# Fri3D_2018_LEDS_01.net
KiCad netlist of a schematic drawn in Altium Designer
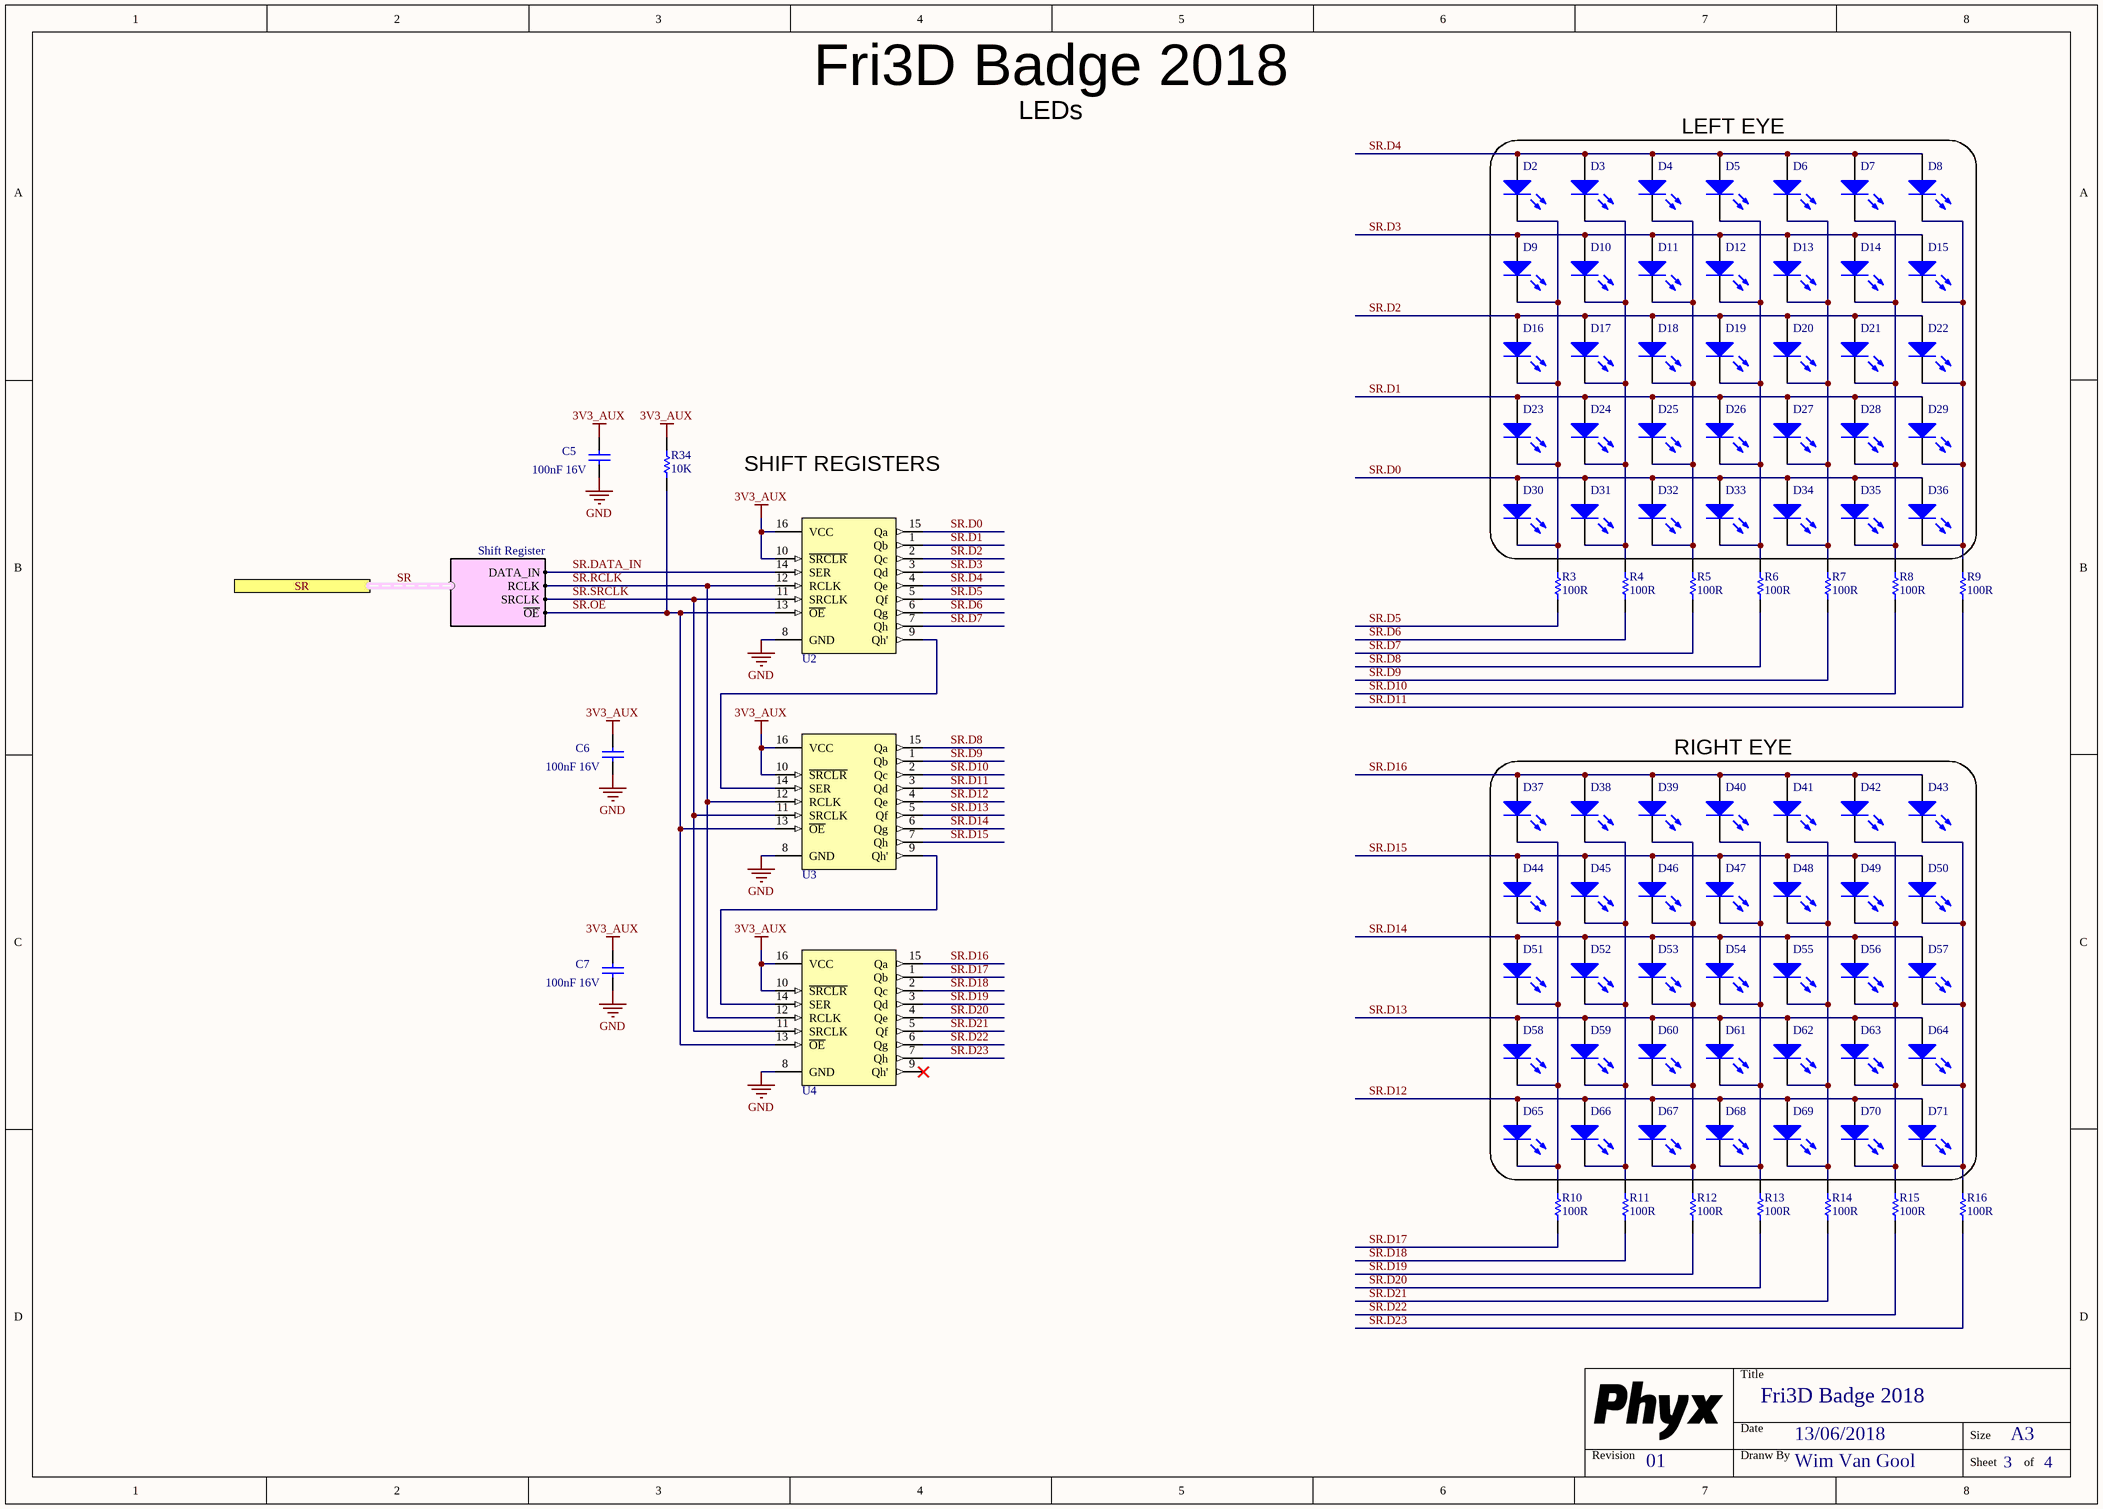
[diagram p0: Fri3D_2018_LEDS_01.SchDoc]

(export (version "E")
  (design (tool "Eeschema 10.0.6"))
  (components
    (comp (ref "C5")
      (value "100nF 16V")
      (footprint "C0603_N")
      (description "Capacitor Ceramic")
      (libsource (lib "Phyx_Components") (part "CAP_CERAMIC"))
    )
    (comp (ref "C6")
      (value "100nF 16V")
      (footprint "C0603_N")
      (description "Capacitor Ceramic")
      (libsource (lib "Phyx_Components") (part "CAP_CERAMIC"))
    )
    (comp (ref "C7")
      (value "100nF 16V")
      (footprint "C0603_N")
      (description "Capacitor Ceramic")
      (libsource (lib "Phyx_Components") (part "CAP_CERAMIC"))
    )
    (comp (ref "D2")
      (value "Default 0805 Blue LED")
      (footprint "LED_0805_BL")
      (description "=Description")
      (libsource (lib "Phyx_Components") (part "LED_BLUE"))
    )
    (comp (ref "D3")
      (value "Default 0805 Blue LED")
      (footprint "LED_0805_BL")
      (description "=Description")
      (libsource (lib "Phyx_Components") (part "LED_BLUE"))
    )
    (comp (ref "D4")
      (value "Default 0805 Blue LED")
      (footprint "LED_0805_BL")
      (description "=Description")
      (libsource (lib "Phyx_Components") (part "LED_BLUE"))
    )
    (comp (ref "D5")
      (value "Default 0805 Blue LED")
      (footprint "LED_0805_BL")
      (description "=Description")
      (libsource (lib "Phyx_Components") (part "LED_BLUE"))
    )
    (comp (ref "D6")
      (value "Default 0805 Blue LED")
      (footprint "LED_0805_BL")
      (description "=Description")
      (libsource (lib "Phyx_Components") (part "LED_BLUE"))
    )
    (comp (ref "D7")
      (value "Default 0805 Blue LED")
      (footprint "LED_0805_BL")
      (description "=Description")
      (libsource (lib "Phyx_Components") (part "LED_BLUE"))
    )
    (comp (ref "D8")
      (value "Default 0805 Blue LED")
      (footprint "LED_0805_BL")
      (description "=Description")
      (libsource (lib "Phyx_Components") (part "LED_BLUE"))
    )
    (comp (ref "D9")
      (value "Default 0805 Blue LED")
      (footprint "LED_0805_BL")
      (description "=Description")
      (libsource (lib "Phyx_Components") (part "LED_BLUE"))
    )
    (comp (ref "D10")
      (value "Default 0805 Blue LED")
      (footprint "LED_0805_BL")
      (description "=Description")
      (libsource (lib "Phyx_Components") (part "LED_BLUE"))
    )
    (comp (ref "D11")
      (value "Default 0805 Blue LED")
      (footprint "LED_0805_BL")
      (description "=Description")
      (libsource (lib "Phyx_Components") (part "LED_BLUE"))
    )
    (comp (ref "D12")
      (value "Default 0805 Blue LED")
      (footprint "LED_0805_BL")
      (description "=Description")
      (libsource (lib "Phyx_Components") (part "LED_BLUE"))
    )
    (comp (ref "D13")
      (value "Default 0805 Blue LED")
      (footprint "LED_0805_BL")
      (description "=Description")
      (libsource (lib "Phyx_Components") (part "LED_BLUE"))
    )
    (comp (ref "D14")
      (value "Default 0805 Blue LED")
      (footprint "LED_0805_BL")
      (description "=Description")
      (libsource (lib "Phyx_Components") (part "LED_BLUE"))
    )
    (comp (ref "D15")
      (value "Default 0805 Blue LED")
      (footprint "LED_0805_BL")
      (description "=Description")
      (libsource (lib "Phyx_Components") (part "LED_BLUE"))
    )
    (comp (ref "D16")
      (value "Default 0805 Blue LED")
      (footprint "LED_0805_BL")
      (description "=Description")
      (libsource (lib "Phyx_Components") (part "LED_BLUE"))
    )
    (comp (ref "D17")
      (value "Default 0805 Blue LED")
      (footprint "LED_0805_BL")
      (description "=Description")
      (libsource (lib "Phyx_Components") (part "LED_BLUE"))
    )
    (comp (ref "D18")
      (value "Default 0805 Blue LED")
      (footprint "LED_0805_BL")
      (description "=Description")
      (libsource (lib "Phyx_Components") (part "LED_BLUE"))
    )
    (comp (ref "D19")
      (value "Default 0805 Blue LED")
      (footprint "LED_0805_BL")
      (description "=Description")
      (libsource (lib "Phyx_Components") (part "LED_BLUE"))
    )
    (comp (ref "D20")
      (value "Default 0805 Blue LED")
      (footprint "LED_0805_BL")
      (description "=Description")
      (libsource (lib "Phyx_Components") (part "LED_BLUE"))
    )
    (comp (ref "D21")
      (value "Default 0805 Blue LED")
      (footprint "LED_0805_BL")
      (description "=Description")
      (libsource (lib "Phyx_Components") (part "LED_BLUE"))
    )
    (comp (ref "D22")
      (value "Default 0805 Blue LED")
      (footprint "LED_0805_BL")
      (description "=Description")
      (libsource (lib "Phyx_Components") (part "LED_BLUE"))
    )
    (comp (ref "D23")
      (value "Default 0805 Blue LED")
      (footprint "LED_0805_BL")
      (description "=Description")
      (libsource (lib "Phyx_Components") (part "LED_BLUE"))
    )
    (comp (ref "D24")
      (value "Default 0805 Blue LED")
      (footprint "LED_0805_BL")
      (description "=Description")
      (libsource (lib "Phyx_Components") (part "LED_BLUE"))
    )
    (comp (ref "D25")
      (value "Default 0805 Blue LED")
      (footprint "LED_0805_BL")
      (description "=Description")
      (libsource (lib "Phyx_Components") (part "LED_BLUE"))
    )
    (comp (ref "D26")
      (value "Default 0805 Blue LED")
      (footprint "LED_0805_BL")
      (description "=Description")
      (libsource (lib "Phyx_Components") (part "LED_BLUE"))
    )
    (comp (ref "D27")
      (value "Default 0805 Blue LED")
      (footprint "LED_0805_BL")
      (description "=Description")
      (libsource (lib "Phyx_Components") (part "LED_BLUE"))
    )
    (comp (ref "D28")
      (value "Default 0805 Blue LED")
      (footprint "LED_0805_BL")
      (description "=Description")
      (libsource (lib "Phyx_Components") (part "LED_BLUE"))
    )
    (comp (ref "D29")
      (value "Default 0805 Blue LED")
      (footprint "LED_0805_BL")
      (description "=Description")
      (libsource (lib "Phyx_Components") (part "LED_BLUE"))
    )
    (comp (ref "D30")
      (value "Default 0805 Blue LED")
      (footprint "LED_0805_BL")
      (description "=Description")
      (libsource (lib "Phyx_Components") (part "LED_BLUE"))
    )
    (comp (ref "D31")
      (value "Default 0805 Blue LED")
      (footprint "LED_0805_BL")
      (description "=Description")
      (libsource (lib "Phyx_Components") (part "LED_BLUE"))
    )
    (comp (ref "D32")
      (value "Default 0805 Blue LED")
      (footprint "LED_0805_BL")
      (description "=Description")
      (libsource (lib "Phyx_Components") (part "LED_BLUE"))
    )
    (comp (ref "D33")
      (value "Default 0805 Blue LED")
      (footprint "LED_0805_BL")
      (description "=Description")
      (libsource (lib "Phyx_Components") (part "LED_BLUE"))
    )
    (comp (ref "D34")
      (value "Default 0805 Blue LED")
      (footprint "LED_0805_BL")
      (description "=Description")
      (libsource (lib "Phyx_Components") (part "LED_BLUE"))
    )
    (comp (ref "D35")
      (value "Default 0805 Blue LED")
      (footprint "LED_0805_BL")
      (description "=Description")
      (libsource (lib "Phyx_Components") (part "LED_BLUE"))
    )
    (comp (ref "D36")
      (value "Default 0805 Blue LED")
      (footprint "LED_0805_BL")
      (description "=Description")
      (libsource (lib "Phyx_Components") (part "LED_BLUE"))
    )
    (comp (ref "D37")
      (value "Default 0805 Blue LED")
      (footprint "LED_0805_BL")
      (description "=Description")
      (libsource (lib "Phyx_Components") (part "LED_BLUE"))
    )
    (comp (ref "D38")
      (value "Default 0805 Blue LED")
      (footprint "LED_0805_BL")
      (description "=Description")
      (libsource (lib "Phyx_Components") (part "LED_BLUE"))
    )
    (comp (ref "D39")
      (value "Default 0805 Blue LED")
      (footprint "LED_0805_BL")
      (description "=Description")
      (libsource (lib "Phyx_Components") (part "LED_BLUE"))
    )
    (comp (ref "D40")
      (value "Default 0805 Blue LED")
      (footprint "LED_0805_BL")
      (description "=Description")
      (libsource (lib "Phyx_Components") (part "LED_BLUE"))
    )
    (comp (ref "D41")
      (value "Default 0805 Blue LED")
      (footprint "LED_0805_BL")
      (description "=Description")
      (libsource (lib "Phyx_Components") (part "LED_BLUE"))
    )
    (comp (ref "D42")
      (value "Default 0805 Blue LED")
      (footprint "LED_0805_BL")
      (description "=Description")
      (libsource (lib "Phyx_Components") (part "LED_BLUE"))
    )
    (comp (ref "D43")
      (value "Default 0805 Blue LED")
      (footprint "LED_0805_BL")
      (description "=Description")
      (libsource (lib "Phyx_Components") (part "LED_BLUE"))
    )
    (comp (ref "D44")
      (value "Default 0805 Blue LED")
      (footprint "LED_0805_BL")
      (description "=Description")
      (libsource (lib "Phyx_Components") (part "LED_BLUE"))
    )
    (comp (ref "D45")
      (value "Default 0805 Blue LED")
      (footprint "LED_0805_BL")
      (description "=Description")
      (libsource (lib "Phyx_Components") (part "LED_BLUE"))
    )
    (comp (ref "D46")
      (value "Default 0805 Blue LED")
      (footprint "LED_0805_BL")
      (description "=Description")
      (libsource (lib "Phyx_Components") (part "LED_BLUE"))
    )
    (comp (ref "D47")
      (value "Default 0805 Blue LED")
      (footprint "LED_0805_BL")
      (description "=Description")
      (libsource (lib "Phyx_Components") (part "LED_BLUE"))
    )
    (comp (ref "D48")
      (value "Default 0805 Blue LED")
      (footprint "LED_0805_BL")
      (description "=Description")
      (libsource (lib "Phyx_Components") (part "LED_BLUE"))
    )
    (comp (ref "D49")
      (value "Default 0805 Blue LED")
      (footprint "LED_0805_BL")
      (description "=Description")
      (libsource (lib "Phyx_Components") (part "LED_BLUE"))
    )
    (comp (ref "D50")
      (value "Default 0805 Blue LED")
      (footprint "LED_0805_BL")
      (description "=Description")
      (libsource (lib "Phyx_Components") (part "LED_BLUE"))
    )
    (comp (ref "D51")
      (value "Default 0805 Blue LED")
      (footprint "LED_0805_BL")
      (description "=Description")
      (libsource (lib "Phyx_Components") (part "LED_BLUE"))
    )
    (comp (ref "D52")
      (value "Default 0805 Blue LED")
      (footprint "LED_0805_BL")
      (description "=Description")
      (libsource (lib "Phyx_Components") (part "LED_BLUE"))
    )
    (comp (ref "D53")
      (value "Default 0805 Blue LED")
      (footprint "LED_0805_BL")
      (description "=Description")
      (libsource (lib "Phyx_Components") (part "LED_BLUE"))
    )
    (comp (ref "D54")
      (value "Default 0805 Blue LED")
      (footprint "LED_0805_BL")
      (description "=Description")
      (libsource (lib "Phyx_Components") (part "LED_BLUE"))
    )
    (comp (ref "D55")
      (value "Default 0805 Blue LED")
      (footprint "LED_0805_BL")
      (description "=Description")
      (libsource (lib "Phyx_Components") (part "LED_BLUE"))
    )
    (comp (ref "D56")
      (value "Default 0805 Blue LED")
      (footprint "LED_0805_BL")
      (description "=Description")
      (libsource (lib "Phyx_Components") (part "LED_BLUE"))
    )
    (comp (ref "D57")
      (value "Default 0805 Blue LED")
      (footprint "LED_0805_BL")
      (description "=Description")
      (libsource (lib "Phyx_Components") (part "LED_BLUE"))
    )
    (comp (ref "D58")
      (value "Default 0805 Blue LED")
      (footprint "LED_0805_BL")
      (description "=Description")
      (libsource (lib "Phyx_Components") (part "LED_BLUE"))
    )
    (comp (ref "D59")
      (value "Default 0805 Blue LED")
      (footprint "LED_0805_BL")
      (description "=Description")
      (libsource (lib "Phyx_Components") (part "LED_BLUE"))
    )
    (comp (ref "D60")
      (value "Default 0805 Blue LED")
      (footprint "LED_0805_BL")
      (description "=Description")
      (libsource (lib "Phyx_Components") (part "LED_BLUE"))
    )
    (comp (ref "D61")
      (value "Default 0805 Blue LED")
      (footprint "LED_0805_BL")
      (description "=Description")
      (libsource (lib "Phyx_Components") (part "LED_BLUE"))
    )
    (comp (ref "D62")
      (value "Default 0805 Blue LED")
      (footprint "LED_0805_BL")
      (description "=Description")
      (libsource (lib "Phyx_Components") (part "LED_BLUE"))
    )
    (comp (ref "D63")
      (value "Default 0805 Blue LED")
      (footprint "LED_0805_BL")
      (description "=Description")
      (libsource (lib "Phyx_Components") (part "LED_BLUE"))
    )
    (comp (ref "D64")
      (value "Default 0805 Blue LED")
      (footprint "LED_0805_BL")
      (description "=Description")
      (libsource (lib "Phyx_Components") (part "LED_BLUE"))
    )
    (comp (ref "D65")
      (value "Default 0805 Blue LED")
      (footprint "LED_0805_BL")
      (description "=Description")
      (libsource (lib "Phyx_Components") (part "LED_BLUE"))
    )
    (comp (ref "D66")
      (value "Default 0805 Blue LED")
      (footprint "LED_0805_BL")
      (description "=Description")
      (libsource (lib "Phyx_Components") (part "LED_BLUE"))
    )
    (comp (ref "D67")
      (value "Default 0805 Blue LED")
      (footprint "LED_0805_BL")
      (description "=Description")
      (libsource (lib "Phyx_Components") (part "LED_BLUE"))
    )
    (comp (ref "D68")
      (value "Default 0805 Blue LED")
      (footprint "LED_0805_BL")
      (description "=Description")
      (libsource (lib "Phyx_Components") (part "LED_BLUE"))
    )
    (comp (ref "D69")
      (value "Default 0805 Blue LED")
      (footprint "LED_0805_BL")
      (description "=Description")
      (libsource (lib "Phyx_Components") (part "LED_BLUE"))
    )
    (comp (ref "D70")
      (value "Default 0805 Blue LED")
      (footprint "LED_0805_BL")
      (description "=Description")
      (libsource (lib "Phyx_Components") (part "LED_BLUE"))
    )
    (comp (ref "D71")
      (value "Default 0805 Blue LED")
      (footprint "LED_0805_BL")
      (description "=Description")
      (libsource (lib "Phyx_Components") (part "LED_BLUE"))
    )
    (comp (ref "R3")
      (value "100R")
      (footprint "R0603_N")
      (fields (field (name "Comment") "RESISTOR"))
      (libsource (lib "Phyx_Components") (part "RESISTOR"))
    )
    (comp (ref "R4")
      (value "100R")
      (footprint "R0603_N")
      (fields (field (name "Comment") "RESISTOR"))
      (libsource (lib "Phyx_Components") (part "RESISTOR"))
    )
    (comp (ref "R5")
      (value "100R")
      (footprint "R0603_N")
      (fields (field (name "Comment") "RESISTOR"))
      (libsource (lib "Phyx_Components") (part "RESISTOR"))
    )
    (comp (ref "R6")
      (value "100R")
      (footprint "R0603_N")
      (fields (field (name "Comment") "RESISTOR"))
      (libsource (lib "Phyx_Components") (part "RESISTOR"))
    )
    (comp (ref "R7")
      (value "100R")
      (footprint "R0603_N")
      (fields (field (name "Comment") "RESISTOR"))
      (libsource (lib "Phyx_Components") (part "RESISTOR"))
    )
    (comp (ref "R8")
      (value "100R")
      (footprint "R0603_N")
      (fields (field (name "Comment") "RESISTOR"))
      (libsource (lib "Phyx_Components") (part "RESISTOR"))
    )
    (comp (ref "R9")
      (value "100R")
      (footprint "R0603_N")
      (fields (field (name "Comment") "RESISTOR"))
      (libsource (lib "Phyx_Components") (part "RESISTOR"))
    )
    (comp (ref "R10")
      (value "100R")
      (footprint "R0603_N")
      (fields (field (name "Comment") "RESISTOR"))
      (libsource (lib "Phyx_Components") (part "RESISTOR"))
    )
    (comp (ref "R11")
      (value "100R")
      (footprint "R0603_N")
      (fields (field (name "Comment") "RESISTOR"))
      (libsource (lib "Phyx_Components") (part "RESISTOR"))
    )
    (comp (ref "R12")
      (value "100R")
      (footprint "R0603_N")
      (fields (field (name "Comment") "RESISTOR"))
      (libsource (lib "Phyx_Components") (part "RESISTOR"))
    )
    (comp (ref "R13")
      (value "100R")
      (footprint "R0603_N")
      (fields (field (name "Comment") "RESISTOR"))
      (libsource (lib "Phyx_Components") (part "RESISTOR"))
    )
    (comp (ref "R14")
      (value "100R")
      (footprint "R0603_N")
      (fields (field (name "Comment") "RESISTOR"))
      (libsource (lib "Phyx_Components") (part "RESISTOR"))
    )
    (comp (ref "R15")
      (value "100R")
      (footprint "R0603_N")
      (fields (field (name "Comment") "RESISTOR"))
      (libsource (lib "Phyx_Components") (part "RESISTOR"))
    )
    (comp (ref "R16")
      (value "100R")
      (footprint "R0603_N")
      (fields (field (name "Comment") "RESISTOR"))
      (libsource (lib "Phyx_Components") (part "RESISTOR"))
    )
    (comp (ref "R34")
      (value "10K")
      (footprint "R0603_N")
      (fields (field (name "Comment") "RESISTOR"))
      (libsource (lib "Phyx_Components") (part "RESISTOR"))
    )
    (comp (ref "U2")
      (value "8-Bit Shift Registers With 3-State Output Registers")
      (footprint "SOIC_N_16")
      (description "=Description")
      (libsource (lib "Phyx_Components") (part "74HC595"))
    )
    (comp (ref "U3")
      (value "8-Bit Shift Registers With 3-State Output Registers")
      (footprint "SOIC_N_16")
      (description "=Description")
      (libsource (lib "Phyx_Components") (part "74HC595"))
    )
    (comp (ref "U4")
      (value "8-Bit Shift Registers With 3-State Output Registers")
      (footprint "SOIC_N_16")
      (description "=Description")
      (libsource (lib "Phyx_Components") (part "74HC595"))
    )
  )
  (nets
    (net (code "3") (name "/SR.D0") (class "Default")
      (node (ref "D30") (pin "1") (pinfunction "A_1") (pintype "passive"))
      (node (ref "D31") (pin "1") (pinfunction "A_1") (pintype "passive"))
      (node (ref "D32") (pin "1") (pinfunction "A_1") (pintype "passive"))
      (node (ref "D33") (pin "1") (pinfunction "A_1") (pintype "passive"))
      (node (ref "D34") (pin "1") (pinfunction "A_1") (pintype "passive"))
      (node (ref "D35") (pin "1") (pinfunction "A_1") (pintype "passive"))
      (node (ref "D36") (pin "1") (pinfunction "A_1") (pintype "passive"))
      (node (ref "U2") (pin "15") (pinfunction "Qa_15") (pintype "output"))
    )
    (net (code "4") (name "/SR.D1") (class "Default")
      (node (ref "D23") (pin "1") (pinfunction "A_1") (pintype "passive"))
      (node (ref "D24") (pin "1") (pinfunction "A_1") (pintype "passive"))
      (node (ref "D25") (pin "1") (pinfunction "A_1") (pintype "passive"))
      (node (ref "D26") (pin "1") (pinfunction "A_1") (pintype "passive"))
      (node (ref "D27") (pin "1") (pinfunction "A_1") (pintype "passive"))
      (node (ref "D28") (pin "1") (pinfunction "A_1") (pintype "passive"))
      (node (ref "D29") (pin "1") (pinfunction "A_1") (pintype "passive"))
      (node (ref "U2") (pin "1") (pinfunction "Qb_1") (pintype "output"))
    )
    (net (code "5") (name "/SR.D2") (class "Default")
      (node (ref "D16") (pin "1") (pinfunction "A_1") (pintype "passive"))
      (node (ref "D17") (pin "1") (pinfunction "A_1") (pintype "passive"))
      (node (ref "D18") (pin "1") (pinfunction "A_1") (pintype "passive"))
      (node (ref "D19") (pin "1") (pinfunction "A_1") (pintype "passive"))
      (node (ref "D20") (pin "1") (pinfunction "A_1") (pintype "passive"))
      (node (ref "D21") (pin "1") (pinfunction "A_1") (pintype "passive"))
      (node (ref "D22") (pin "1") (pinfunction "A_1") (pintype "passive"))
      (node (ref "U2") (pin "2") (pinfunction "Qc_2") (pintype "output"))
    )
    (net (code "6") (name "/SR.D3") (class "Default")
      (node (ref "D10") (pin "1") (pinfunction "A_1") (pintype "passive"))
      (node (ref "D11") (pin "1") (pinfunction "A_1") (pintype "passive"))
      (node (ref "D12") (pin "1") (pinfunction "A_1") (pintype "passive"))
      (node (ref "D13") (pin "1") (pinfunction "A_1") (pintype "passive"))
      (node (ref "D14") (pin "1") (pinfunction "A_1") (pintype "passive"))
      (node (ref "D15") (pin "1") (pinfunction "A_1") (pintype "passive"))
      (node (ref "D9") (pin "1") (pinfunction "A_1") (pintype "passive"))
      (node (ref "U2") (pin "3") (pinfunction "Qd_3") (pintype "output"))
    )
    (net (code "7") (name "/SR.D4") (class "Default")
      (node (ref "D2") (pin "1") (pinfunction "A_1") (pintype "passive"))
      (node (ref "D3") (pin "1") (pinfunction "A_1") (pintype "passive"))
      (node (ref "D4") (pin "1") (pinfunction "A_1") (pintype "passive"))
      (node (ref "D5") (pin "1") (pinfunction "A_1") (pintype "passive"))
      (node (ref "D6") (pin "1") (pinfunction "A_1") (pintype "passive"))
      (node (ref "D7") (pin "1") (pinfunction "A_1") (pintype "passive"))
      (node (ref "D8") (pin "1") (pinfunction "A_1") (pintype "passive"))
      (node (ref "U2") (pin "4") (pinfunction "Qe_4") (pintype "output"))
    )
    (net (code "8") (name "/SR.D5") (class "Default")
      (node (ref "R3") (pin "2") (pinfunction "2_2") (pintype "passive"))
      (node (ref "U2") (pin "5") (pinfunction "Qf_5") (pintype "output"))
    )
    (net (code "9") (name "/SR.D6") (class "Default")
      (node (ref "R4") (pin "2") (pinfunction "2_2") (pintype "passive"))
      (node (ref "U2") (pin "6") (pinfunction "Qg_6") (pintype "output"))
    )
    (net (code "10") (name "/SR.D7") (class "Default")
      (node (ref "R5") (pin "2") (pinfunction "2_2") (pintype "passive"))
      (node (ref "U2") (pin "7") (pinfunction "Qh_7") (pintype "output"))
    )
    (net (code "11") (name "/SR.D8") (class "Default")
      (node (ref "R6") (pin "2") (pinfunction "2_2") (pintype "passive"))
      (node (ref "U3") (pin "15") (pinfunction "Qa_15") (pintype "output"))
    )
    (net (code "12") (name "/SR.D9") (class "Default")
      (node (ref "R7") (pin "2") (pinfunction "2_2") (pintype "passive"))
      (node (ref "U3") (pin "1") (pinfunction "Qb_1") (pintype "output"))
    )
    (net (code "13") (name "/SR.D10") (class "Default")
      (node (ref "R8") (pin "2") (pinfunction "2_2") (pintype "passive"))
      (node (ref "U3") (pin "2") (pinfunction "Qc_2") (pintype "output"))
    )
    (net (code "14") (name "/SR.D11") (class "Default")
      (node (ref "R9") (pin "2") (pinfunction "2_2") (pintype "passive"))
      (node (ref "U3") (pin "3") (pinfunction "Qd_3") (pintype "output"))
    )
    (net (code "15") (name "/SR.D12") (class "Default")
      (node (ref "D65") (pin "1") (pinfunction "A_1") (pintype "passive"))
      (node (ref "D66") (pin "1") (pinfunction "A_1") (pintype "passive"))
      (node (ref "D67") (pin "1") (pinfunction "A_1") (pintype "passive"))
      (node (ref "D68") (pin "1") (pinfunction "A_1") (pintype "passive"))
      (node (ref "D69") (pin "1") (pinfunction "A_1") (pintype "passive"))
      (node (ref "D70") (pin "1") (pinfunction "A_1") (pintype "passive"))
      (node (ref "D71") (pin "1") (pinfunction "A_1") (pintype "passive"))
      (node (ref "U3") (pin "4") (pinfunction "Qe_4") (pintype "output"))
    )
    (net (code "16") (name "/SR.D13") (class "Default")
      (node (ref "D58") (pin "1") (pinfunction "A_1") (pintype "passive"))
      (node (ref "D59") (pin "1") (pinfunction "A_1") (pintype "passive"))
      (node (ref "D60") (pin "1") (pinfunction "A_1") (pintype "passive"))
      (node (ref "D61") (pin "1") (pinfunction "A_1") (pintype "passive"))
      (node (ref "D62") (pin "1") (pinfunction "A_1") (pintype "passive"))
      (node (ref "D63") (pin "1") (pinfunction "A_1") (pintype "passive"))
      (node (ref "D64") (pin "1") (pinfunction "A_1") (pintype "passive"))
      (node (ref "U3") (pin "5") (pinfunction "Qf_5") (pintype "output"))
    )
    (net (code "17") (name "/SR.D14") (class "Default")
      (node (ref "D51") (pin "1") (pinfunction "A_1") (pintype "passive"))
      (node (ref "D52") (pin "1") (pinfunction "A_1") (pintype "passive"))
      (node (ref "D53") (pin "1") (pinfunction "A_1") (pintype "passive"))
      (node (ref "D54") (pin "1") (pinfunction "A_1") (pintype "passive"))
      (node (ref "D55") (pin "1") (pinfunction "A_1") (pintype "passive"))
      (node (ref "D56") (pin "1") (pinfunction "A_1") (pintype "passive"))
      (node (ref "D57") (pin "1") (pinfunction "A_1") (pintype "passive"))
      (node (ref "U3") (pin "6") (pinfunction "Qg_6") (pintype "output"))
    )
    (net (code "18") (name "/SR.D15") (class "Default")
      (node (ref "D44") (pin "1") (pinfunction "A_1") (pintype "passive"))
      (node (ref "D45") (pin "1") (pinfunction "A_1") (pintype "passive"))
      (node (ref "D46") (pin "1") (pinfunction "A_1") (pintype "passive"))
      (node (ref "D47") (pin "1") (pinfunction "A_1") (pintype "passive"))
      (node (ref "D48") (pin "1") (pinfunction "A_1") (pintype "passive"))
      (node (ref "D49") (pin "1") (pinfunction "A_1") (pintype "passive"))
      (node (ref "D50") (pin "1") (pinfunction "A_1") (pintype "passive"))
      (node (ref "U3") (pin "7") (pinfunction "Qh_7") (pintype "output"))
    )
    (net (code "19") (name "/SR.D16") (class "Default")
      (node (ref "D37") (pin "1") (pinfunction "A_1") (pintype "passive"))
      (node (ref "D38") (pin "1") (pinfunction "A_1") (pintype "passive"))
      (node (ref "D39") (pin "1") (pinfunction "A_1") (pintype "passive"))
      (node (ref "D40") (pin "1") (pinfunction "A_1") (pintype "passive"))
      (node (ref "D41") (pin "1") (pinfunction "A_1") (pintype "passive"))
      (node (ref "D42") (pin "1") (pinfunction "A_1") (pintype "passive"))
      (node (ref "D43") (pin "1") (pinfunction "A_1") (pintype "passive"))
      (node (ref "U4") (pin "15") (pinfunction "Qa_15") (pintype "output"))
    )
    (net (code "20") (name "/SR.D17") (class "Default")
      (node (ref "R10") (pin "2") (pinfunction "2_2") (pintype "passive"))
      (node (ref "U4") (pin "1") (pinfunction "Qb_1") (pintype "output"))
    )
    (net (code "21") (name "/SR.D18") (class "Default")
      (node (ref "R11") (pin "2") (pinfunction "2_2") (pintype "passive"))
      (node (ref "U4") (pin "2") (pinfunction "Qc_2") (pintype "output"))
    )
    (net (code "22") (name "/SR.D19") (class "Default")
      (node (ref "R12") (pin "2") (pinfunction "2_2") (pintype "passive"))
      (node (ref "U4") (pin "3") (pinfunction "Qd_3") (pintype "output"))
    )
    (net (code "23") (name "/SR.D20") (class "Default")
      (node (ref "R13") (pin "2") (pinfunction "2_2") (pintype "passive"))
      (node (ref "U4") (pin "4") (pinfunction "Qe_4") (pintype "output"))
    )
    (net (code "24") (name "/SR.D21") (class "Default")
      (node (ref "R14") (pin "2") (pinfunction "2_2") (pintype "passive"))
      (node (ref "U4") (pin "5") (pinfunction "Qf_5") (pintype "output"))
    )
    (net (code "25") (name "/SR.D22") (class "Default")
      (node (ref "R15") (pin "2") (pinfunction "2_2") (pintype "passive"))
      (node (ref "U4") (pin "6") (pinfunction "Qg_6") (pintype "output"))
    )
    (net (code "26") (name "/SR.D23") (class "Default")
      (node (ref "R16") (pin "2") (pinfunction "2_2") (pintype "passive"))
      (node (ref "U4") (pin "7") (pinfunction "Qh_7") (pintype "output"))
    )
    (net (code "27") (name "/SR.DATA_IN") (class "Default")
      (node (ref "U2") (pin "14") (pinfunction "SER_14") (pintype "input"))
    )
    (net (code "28") (name "/SR.RCLK") (class "Default")
      (node (ref "U2") (pin "12") (pinfunction "RCLK_12") (pintype "input"))
      (node (ref "U3") (pin "12") (pinfunction "RCLK_12") (pintype "input"))
      (node (ref "U4") (pin "12") (pinfunction "RCLK_12") (pintype "input"))
    )
    (net (code "29") (name "/SR.SRCLK") (class "Default")
      (node (ref "U2") (pin "11") (pinfunction "SRCLK_11") (pintype "input"))
      (node (ref "U3") (pin "11") (pinfunction "SRCLK_11") (pintype "input"))
      (node (ref "U4") (pin "11") (pinfunction "SRCLK_11") (pintype "input"))
    )
    (net (code "30") (name "/SR.~{OE}") (class "Default")
      (node (ref "R34") (pin "2") (pinfunction "2_2") (pintype "passive"))
      (node (ref "U2") (pin "13") (pinfunction "~{OE}_13") (pintype "input"))
      (node (ref "U3") (pin "13") (pinfunction "~{OE}_13") (pintype "input"))
      (node (ref "U4") (pin "13") (pinfunction "~{OE}_13") (pintype "input"))
    )
    (net (code "32") (name "3V3_AUX") (class "Default")
      (node (ref "C5") (pin "1") (pinfunction "1_1") (pintype "passive"))
      (node (ref "C6") (pin "1") (pinfunction "1_1") (pintype "passive"))
      (node (ref "C7") (pin "1") (pinfunction "1_1") (pintype "passive"))
      (node (ref "R34") (pin "1") (pinfunction "1_1") (pintype "passive"))
      (node (ref "U2") (pin "10") (pinfunction "~{SRCLR}_10") (pintype "input"))
      (node (ref "U2") (pin "16") (pinfunction "VCC_16") (pintype "power_in"))
      (node (ref "U3") (pin "10") (pinfunction "~{SRCLR}_10") (pintype "input"))
      (node (ref "U3") (pin "16") (pinfunction "VCC_16") (pintype "power_in"))
      (node (ref "U4") (pin "10") (pinfunction "~{SRCLR}_10") (pintype "input"))
      (node (ref "U4") (pin "16") (pinfunction "VCC_16") (pintype "power_in"))
    )
    (net (code "33") (name "GND") (class "Default")
      (node (ref "C5") (pin "2") (pinfunction "2_2") (pintype "passive"))
      (node (ref "C6") (pin "2") (pinfunction "2_2") (pintype "passive"))
      (node (ref "C7") (pin "2") (pinfunction "2_2") (pintype "passive"))
      (node (ref "U2") (pin "8") (pinfunction "GND_8") (pintype "power_in"))
      (node (ref "U3") (pin "8") (pinfunction "GND_8") (pintype "power_in"))
      (node (ref "U4") (pin "8") (pinfunction "GND_8") (pintype "power_in"))
    )
    (net (code "34") (name "Net-(D10-K)") (class "Default")
      (node (ref "D10") (pin "2") (pinfunction "K_2") (pintype "passive"))
      (node (ref "D17") (pin "2") (pinfunction "K_2") (pintype "passive"))
      (node (ref "D24") (pin "2") (pinfunction "K_2") (pintype "passive"))
      (node (ref "D3") (pin "2") (pinfunction "K_2") (pintype "passive"))
      (node (ref "D31") (pin "2") (pinfunction "K_2") (pintype "passive"))
      (node (ref "R4") (pin "1") (pinfunction "1_1") (pintype "passive"))
    )
    (net (code "35") (name "Net-(D11-K)") (class "Default")
      (node (ref "D11") (pin "2") (pinfunction "K_2") (pintype "passive"))
      (node (ref "D18") (pin "2") (pinfunction "K_2") (pintype "passive"))
      (node (ref "D25") (pin "2") (pinfunction "K_2") (pintype "passive"))
      (node (ref "D32") (pin "2") (pinfunction "K_2") (pintype "passive"))
      (node (ref "D4") (pin "2") (pinfunction "K_2") (pintype "passive"))
      (node (ref "R5") (pin "1") (pinfunction "1_1") (pintype "passive"))
    )
    (net (code "36") (name "Net-(D12-K)") (class "Default")
      (node (ref "D12") (pin "2") (pinfunction "K_2") (pintype "passive"))
      (node (ref "D19") (pin "2") (pinfunction "K_2") (pintype "passive"))
      (node (ref "D26") (pin "2") (pinfunction "K_2") (pintype "passive"))
      (node (ref "D33") (pin "2") (pinfunction "K_2") (pintype "passive"))
      (node (ref "D5") (pin "2") (pinfunction "K_2") (pintype "passive"))
      (node (ref "R6") (pin "1") (pinfunction "1_1") (pintype "passive"))
    )
    (net (code "37") (name "Net-(D13-K)") (class "Default")
      (node (ref "D13") (pin "2") (pinfunction "K_2") (pintype "passive"))
      (node (ref "D20") (pin "2") (pinfunction "K_2") (pintype "passive"))
      (node (ref "D27") (pin "2") (pinfunction "K_2") (pintype "passive"))
      (node (ref "D34") (pin "2") (pinfunction "K_2") (pintype "passive"))
      (node (ref "D6") (pin "2") (pinfunction "K_2") (pintype "passive"))
      (node (ref "R7") (pin "1") (pinfunction "1_1") (pintype "passive"))
    )
    (net (code "38") (name "Net-(D14-K)") (class "Default")
      (node (ref "D14") (pin "2") (pinfunction "K_2") (pintype "passive"))
      (node (ref "D21") (pin "2") (pinfunction "K_2") (pintype "passive"))
      (node (ref "D28") (pin "2") (pinfunction "K_2") (pintype "passive"))
      (node (ref "D35") (pin "2") (pinfunction "K_2") (pintype "passive"))
      (node (ref "D7") (pin "2") (pinfunction "K_2") (pintype "passive"))
      (node (ref "R8") (pin "1") (pinfunction "1_1") (pintype "passive"))
    )
    (net (code "39") (name "Net-(D15-K)") (class "Default")
      (node (ref "D15") (pin "2") (pinfunction "K_2") (pintype "passive"))
      (node (ref "D22") (pin "2") (pinfunction "K_2") (pintype "passive"))
      (node (ref "D29") (pin "2") (pinfunction "K_2") (pintype "passive"))
      (node (ref "D36") (pin "2") (pinfunction "K_2") (pintype "passive"))
      (node (ref "D8") (pin "2") (pinfunction "K_2") (pintype "passive"))
      (node (ref "R9") (pin "1") (pinfunction "1_1") (pintype "passive"))
    )
    (net (code "40") (name "Net-(D16-K)") (class "Default")
      (node (ref "D16") (pin "2") (pinfunction "K_2") (pintype "passive"))
      (node (ref "D2") (pin "2") (pinfunction "K_2") (pintype "passive"))
      (node (ref "D23") (pin "2") (pinfunction "K_2") (pintype "passive"))
      (node (ref "D30") (pin "2") (pinfunction "K_2") (pintype "passive"))
      (node (ref "D9") (pin "2") (pinfunction "K_2") (pintype "passive"))
      (node (ref "R3") (pin "1") (pinfunction "1_1") (pintype "passive"))
    )
    (net (code "41") (name "Net-(D37-K)") (class "Default")
      (node (ref "D37") (pin "2") (pinfunction "K_2") (pintype "passive"))
      (node (ref "D44") (pin "2") (pinfunction "K_2") (pintype "passive"))
      (node (ref "D51") (pin "2") (pinfunction "K_2") (pintype "passive"))
      (node (ref "D58") (pin "2") (pinfunction "K_2") (pintype "passive"))
      (node (ref "D65") (pin "2") (pinfunction "K_2") (pintype "passive"))
      (node (ref "R10") (pin "1") (pinfunction "1_1") (pintype "passive"))
    )
    (net (code "42") (name "Net-(D38-K)") (class "Default")
      (node (ref "D38") (pin "2") (pinfunction "K_2") (pintype "passive"))
      (node (ref "D45") (pin "2") (pinfunction "K_2") (pintype "passive"))
      (node (ref "D52") (pin "2") (pinfunction "K_2") (pintype "passive"))
      (node (ref "D59") (pin "2") (pinfunction "K_2") (pintype "passive"))
      (node (ref "D66") (pin "2") (pinfunction "K_2") (pintype "passive"))
      (node (ref "R11") (pin "1") (pinfunction "1_1") (pintype "passive"))
    )
    (net (code "43") (name "Net-(D39-K)") (class "Default")
      (node (ref "D39") (pin "2") (pinfunction "K_2") (pintype "passive"))
      (node (ref "D46") (pin "2") (pinfunction "K_2") (pintype "passive"))
      (node (ref "D53") (pin "2") (pinfunction "K_2") (pintype "passive"))
      (node (ref "D60") (pin "2") (pinfunction "K_2") (pintype "passive"))
      (node (ref "D67") (pin "2") (pinfunction "K_2") (pintype "passive"))
      (node (ref "R12") (pin "1") (pinfunction "1_1") (pintype "passive"))
    )
    (net (code "44") (name "Net-(D40-K)") (class "Default")
      (node (ref "D40") (pin "2") (pinfunction "K_2") (pintype "passive"))
      (node (ref "D47") (pin "2") (pinfunction "K_2") (pintype "passive"))
      (node (ref "D54") (pin "2") (pinfunction "K_2") (pintype "passive"))
      (node (ref "D61") (pin "2") (pinfunction "K_2") (pintype "passive"))
      (node (ref "D68") (pin "2") (pinfunction "K_2") (pintype "passive"))
      (node (ref "R13") (pin "1") (pinfunction "1_1") (pintype "passive"))
    )
    (net (code "45") (name "Net-(D41-K)") (class "Default")
      (node (ref "D41") (pin "2") (pinfunction "K_2") (pintype "passive"))
      (node (ref "D48") (pin "2") (pinfunction "K_2") (pintype "passive"))
      (node (ref "D55") (pin "2") (pinfunction "K_2") (pintype "passive"))
      (node (ref "D62") (pin "2") (pinfunction "K_2") (pintype "passive"))
      (node (ref "D69") (pin "2") (pinfunction "K_2") (pintype "passive"))
      (node (ref "R14") (pin "1") (pinfunction "1_1") (pintype "passive"))
    )
    (net (code "46") (name "Net-(D42-K)") (class "Default")
      (node (ref "D42") (pin "2") (pinfunction "K_2") (pintype "passive"))
      (node (ref "D49") (pin "2") (pinfunction "K_2") (pintype "passive"))
      (node (ref "D56") (pin "2") (pinfunction "K_2") (pintype "passive"))
      (node (ref "D63") (pin "2") (pinfunction "K_2") (pintype "passive"))
      (node (ref "D70") (pin "2") (pinfunction "K_2") (pintype "passive"))
      (node (ref "R15") (pin "1") (pinfunction "1_1") (pintype "passive"))
    )
    (net (code "47") (name "Net-(D43-K)") (class "Default")
      (node (ref "D43") (pin "2") (pinfunction "K_2") (pintype "passive"))
      (node (ref "D50") (pin "2") (pinfunction "K_2") (pintype "passive"))
      (node (ref "D57") (pin "2") (pinfunction "K_2") (pintype "passive"))
      (node (ref "D64") (pin "2") (pinfunction "K_2") (pintype "passive"))
      (node (ref "D71") (pin "2") (pinfunction "K_2") (pintype "passive"))
      (node (ref "R16") (pin "1") (pinfunction "1_1") (pintype "passive"))
    )
    (net (code "48") (name "Net-(U2-Qh')") (class "Default")
      (node (ref "U2") (pin "9") (pinfunction "Qh'_9") (pintype "output"))
      (node (ref "U3") (pin "14") (pinfunction "SER_14") (pintype "input"))
    )
    (net (code "49") (name "Net-(U3-Qh')") (class "Default")
      (node (ref "U3") (pin "9") (pinfunction "Qh'_9") (pintype "output"))
      (node (ref "U4") (pin "14") (pinfunction "SER_14") (pintype "input"))
    )
    (net (code "50") (name "unconnected-(U4-Qh'-Pad9)") (class "Default")
      (node (ref "U4") (pin "9") (pinfunction "Qh'_9") (pintype "output+no_connect"))
    )
  )
)
